# gal_pla_smd_ii.net
KiCad netlist of a schematic drawn in EAGLE
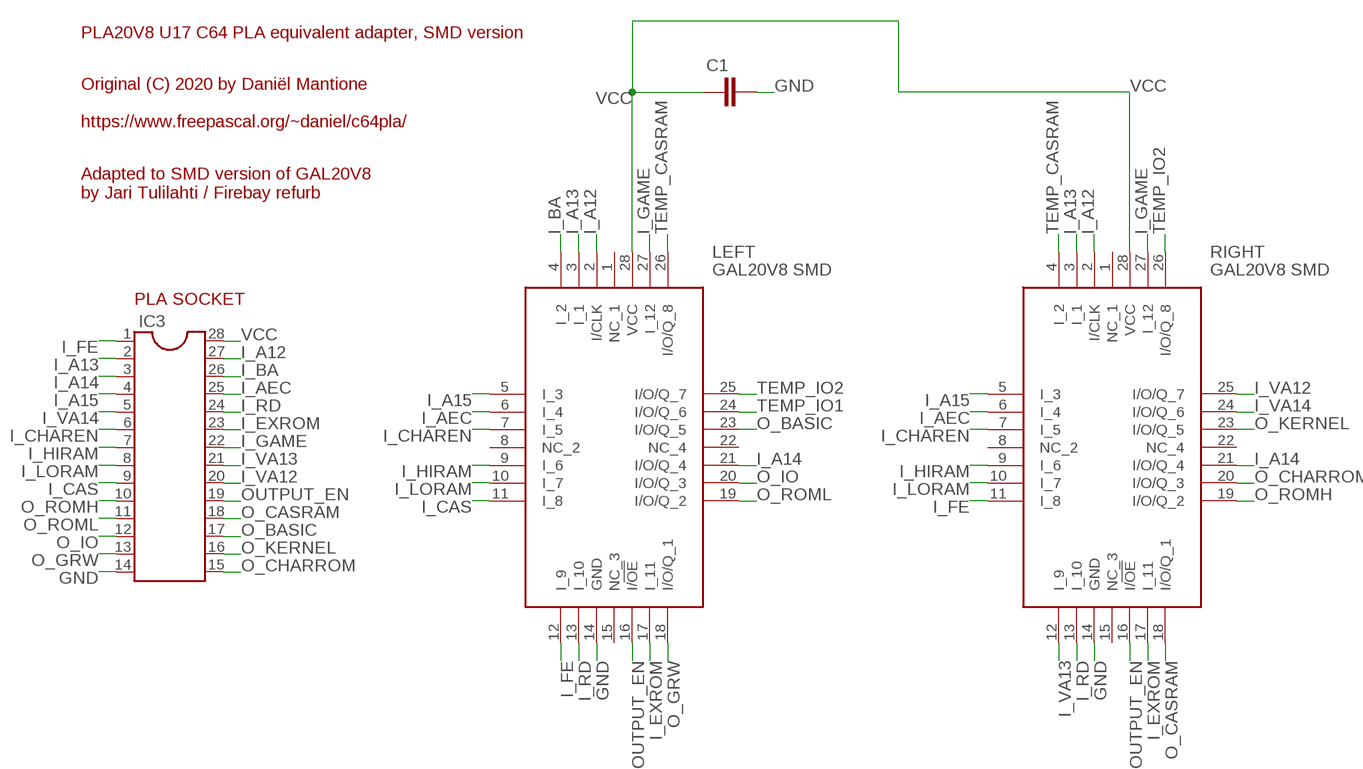
[diagram p0: schematic, sheet 1]

(export (version "E")
  (design (tool "Eeschema 10.0.6"))
  (components
    (comp (ref "C1")
      (value "CAP0603-CAP")
      (footprint "eagle-import:0603-CAP")
      (libsource (lib "eagle-import") (part "CAP0603-CAP"))
    )
    (comp (ref "IC3")
      (value "DIL28")
      (footprint "eagle-import:DIL28-6")
      (libsource (lib "eagle-import") (part "DIL28"))
    )
    (comp (ref "LEFT")
      (value "GAL20V8 SMD")
      (footprint "eagle-import:PLCC127P1245X1245X457-28N")
      (fields (field (name "MANUFACTURER_PART_NUMBER") "GAL20V8B-10LJI"))
      (libsource (lib "eagle-import") (part "GAL20V8B-10LJI"))
    )
    (comp (ref "RIGHT")
      (value "GAL20V8 SMD")
      (footprint "eagle-import:PLCC127P1245X1245X457-28N")
      (fields (field (name "MANUFACTURER_PART_NUMBER") "GAL20V8B-10LJI"))
      (libsource (lib "eagle-import") (part "GAL20V8B-10LJI"))
    )
  )
  (nets
    (net (code "1") (name "GND") (class "Default")
      (node (ref "C1") (pin "2") (pinfunction "2_2") (pintype "passive"))
      (node (ref "IC3") (pin "14") (pinfunction "14_14") (pintype "passive"))
      (node (ref "LEFT") (pin "14") (pinfunction "GND_14") (pintype "bidirectional"))
      (node (ref "RIGHT") (pin "14") (pinfunction "GND_14") (pintype "bidirectional"))
    )
    (net (code "2") (name "I_A12") (class "Default")
      (node (ref "IC3") (pin "27") (pinfunction "27_27") (pintype "passive"))
      (node (ref "LEFT") (pin "2") (pinfunction "I/CLK_2") (pintype "bidirectional"))
      (node (ref "RIGHT") (pin "2") (pinfunction "I/CLK_2") (pintype "bidirectional"))
    )
    (net (code "3") (name "I_A13") (class "Default")
      (node (ref "IC3") (pin "2") (pinfunction "2_2") (pintype "passive"))
      (node (ref "LEFT") (pin "3") (pinfunction "I_1_3") (pintype "bidirectional"))
      (node (ref "RIGHT") (pin "3") (pinfunction "I_1_3") (pintype "bidirectional"))
    )
    (net (code "4") (name "I_A14") (class "Default")
      (node (ref "IC3") (pin "3") (pinfunction "3_3") (pintype "passive"))
      (node (ref "LEFT") (pin "21") (pinfunction "I/O/Q_4_21") (pintype "bidirectional"))
      (node (ref "RIGHT") (pin "21") (pinfunction "I/O/Q_4_21") (pintype "bidirectional"))
    )
    (net (code "5") (name "I_A15") (class "Default")
      (node (ref "IC3") (pin "4") (pinfunction "4_4") (pintype "passive"))
      (node (ref "LEFT") (pin "5") (pinfunction "I_3_5") (pintype "bidirectional"))
      (node (ref "RIGHT") (pin "5") (pinfunction "I_3_5") (pintype "bidirectional"))
    )
    (net (code "6") (name "I_AEC") (class "Default")
      (node (ref "IC3") (pin "25") (pinfunction "25_25") (pintype "passive"))
      (node (ref "LEFT") (pin "6") (pinfunction "I_4_6") (pintype "bidirectional"))
      (node (ref "RIGHT") (pin "6") (pinfunction "I_4_6") (pintype "bidirectional"))
    )
    (net (code "7") (name "I_BA") (class "Default")
      (node (ref "IC3") (pin "26") (pinfunction "26_26") (pintype "passive"))
      (node (ref "LEFT") (pin "4") (pinfunction "I_2_4") (pintype "bidirectional"))
    )
    (net (code "8") (name "I_CAS") (class "Default")
      (node (ref "IC3") (pin "9") (pinfunction "9_9") (pintype "passive"))
      (node (ref "LEFT") (pin "11") (pinfunction "I_8_11") (pintype "bidirectional"))
    )
    (net (code "9") (name "I_CHAREN") (class "Default")
      (node (ref "IC3") (pin "6") (pinfunction "6_6") (pintype "passive"))
      (node (ref "LEFT") (pin "7") (pinfunction "I_5_7") (pintype "bidirectional"))
      (node (ref "RIGHT") (pin "7") (pinfunction "I_5_7") (pintype "bidirectional"))
    )
    (net (code "10") (name "I_EXROM") (class "Default")
      (node (ref "IC3") (pin "23") (pinfunction "23_23") (pintype "passive"))
      (node (ref "LEFT") (pin "17") (pinfunction "I_11_17") (pintype "bidirectional"))
      (node (ref "RIGHT") (pin "17") (pinfunction "I_11_17") (pintype "bidirectional"))
    )
    (net (code "11") (name "I_FE") (class "Default")
      (node (ref "IC3") (pin "1") (pinfunction "1_1") (pintype "passive"))
      (node (ref "LEFT") (pin "12") (pinfunction "I_9_12") (pintype "bidirectional"))
      (node (ref "RIGHT") (pin "11") (pinfunction "I_8_11") (pintype "bidirectional"))
    )
    (net (code "12") (name "I_GAME") (class "Default")
      (node (ref "IC3") (pin "22") (pinfunction "22_22") (pintype "passive"))
      (node (ref "LEFT") (pin "27") (pinfunction "I_12_27") (pintype "bidirectional"))
      (node (ref "RIGHT") (pin "27") (pinfunction "I_12_27") (pintype "bidirectional"))
    )
    (net (code "13") (name "I_HIRAM") (class "Default")
      (node (ref "IC3") (pin "7") (pinfunction "7_7") (pintype "passive"))
      (node (ref "LEFT") (pin "9") (pinfunction "I_6_9") (pintype "bidirectional"))
      (node (ref "RIGHT") (pin "9") (pinfunction "I_6_9") (pintype "bidirectional"))
    )
    (net (code "14") (name "I_LORAM") (class "Default")
      (node (ref "IC3") (pin "8") (pinfunction "8_8") (pintype "passive"))
      (node (ref "LEFT") (pin "10") (pinfunction "I_7_10") (pintype "bidirectional"))
      (node (ref "RIGHT") (pin "10") (pinfunction "I_7_10") (pintype "bidirectional"))
    )
    (net (code "15") (name "I_RD") (class "Default")
      (node (ref "IC3") (pin "24") (pinfunction "24_24") (pintype "passive"))
      (node (ref "LEFT") (pin "13") (pinfunction "I_10_13") (pintype "bidirectional"))
      (node (ref "RIGHT") (pin "13") (pinfunction "I_10_13") (pintype "bidirectional"))
    )
    (net (code "16") (name "I_VA12") (class "Default")
      (node (ref "IC3") (pin "20") (pinfunction "20_20") (pintype "passive"))
      (node (ref "RIGHT") (pin "25") (pinfunction "I/O/Q_7_25") (pintype "bidirectional"))
    )
    (net (code "17") (name "I_VA13") (class "Default")
      (node (ref "IC3") (pin "21") (pinfunction "21_21") (pintype "passive"))
      (node (ref "RIGHT") (pin "12") (pinfunction "I_9_12") (pintype "bidirectional"))
    )
    (net (code "18") (name "I_VA14") (class "Default")
      (node (ref "IC3") (pin "5") (pinfunction "5_5") (pintype "passive"))
      (node (ref "RIGHT") (pin "24") (pinfunction "I/O/Q_6_24") (pintype "bidirectional"))
    )
    (net (code "19") (name "OUTPUT_EN") (class "Default")
      (node (ref "IC3") (pin "19") (pinfunction "19_19") (pintype "passive"))
      (node (ref "LEFT") (pin "16") (pinfunction "I/~{OE}_16") (pintype "bidirectional"))
      (node (ref "RIGHT") (pin "16") (pinfunction "I/~{OE}_16") (pintype "bidirectional"))
    )
    (net (code "20") (name "O_BASIC") (class "Default")
      (node (ref "IC3") (pin "17") (pinfunction "17_17") (pintype "passive"))
      (node (ref "LEFT") (pin "23") (pinfunction "I/O/Q_5_23") (pintype "bidirectional"))
    )
    (net (code "21") (name "O_CASRAM") (class "Default")
      (node (ref "IC3") (pin "18") (pinfunction "18_18") (pintype "passive"))
      (node (ref "RIGHT") (pin "18") (pinfunction "I/O/Q_1_18") (pintype "bidirectional"))
    )
    (net (code "22") (name "O_CHARROM") (class "Default")
      (node (ref "IC3") (pin "15") (pinfunction "15_15") (pintype "passive"))
      (node (ref "RIGHT") (pin "20") (pinfunction "I/O/Q_3_20") (pintype "bidirectional"))
    )
    (net (code "23") (name "O_GRW") (class "Default")
      (node (ref "IC3") (pin "13") (pinfunction "13_13") (pintype "passive"))
      (node (ref "LEFT") (pin "18") (pinfunction "I/O/Q_1_18") (pintype "bidirectional"))
    )
    (net (code "24") (name "O_IO") (class "Default")
      (node (ref "IC3") (pin "12") (pinfunction "12_12") (pintype "passive"))
      (node (ref "LEFT") (pin "20") (pinfunction "I/O/Q_3_20") (pintype "bidirectional"))
    )
    (net (code "25") (name "O_KERNEL") (class "Default")
      (node (ref "IC3") (pin "16") (pinfunction "16_16") (pintype "passive"))
      (node (ref "RIGHT") (pin "23") (pinfunction "I/O/Q_5_23") (pintype "bidirectional"))
    )
    (net (code "26") (name "O_ROMH") (class "Default")
      (node (ref "IC3") (pin "10") (pinfunction "10_10") (pintype "passive"))
      (node (ref "RIGHT") (pin "19") (pinfunction "I/O/Q_2_19") (pintype "bidirectional"))
    )
    (net (code "27") (name "O_ROML") (class "Default")
      (node (ref "IC3") (pin "11") (pinfunction "11_11") (pintype "passive"))
      (node (ref "LEFT") (pin "19") (pinfunction "I/O/Q_2_19") (pintype "bidirectional"))
    )
    (net (code "28") (name "TEMP_CASRAM") (class "Default")
      (node (ref "LEFT") (pin "26") (pinfunction "I/O/Q_8_26") (pintype "bidirectional"))
      (node (ref "RIGHT") (pin "4") (pinfunction "I_2_4") (pintype "bidirectional"))
    )
    (net (code "29") (name "TEMP_IO1") (class "Default")
      (node (ref "LEFT") (pin "24") (pinfunction "I/O/Q_6_24") (pintype "bidirectional"))
    )
    (net (code "30") (name "TEMP_IO2") (class "Default")
      (node (ref "LEFT") (pin "25") (pinfunction "I/O/Q_7_25") (pintype "bidirectional"))
      (node (ref "RIGHT") (pin "26") (pinfunction "I/O/Q_8_26") (pintype "bidirectional"))
    )
    (net (code "31") (name "VCC") (class "Default")
      (node (ref "C1") (pin "1") (pinfunction "1_1") (pintype "passive"))
      (node (ref "IC3") (pin "28") (pinfunction "28_28") (pintype "passive"))
      (node (ref "LEFT") (pin "28") (pinfunction "VCC_28") (pintype "bidirectional"))
      (node (ref "RIGHT") (pin "28") (pinfunction "VCC_28") (pintype "bidirectional"))
    )
    (net (code "32") (name "unconnected-(LEFT-NC_1-Pad1)") (class "Default")
      (node (ref "LEFT") (pin "1") (pinfunction "NC_1_1") (pintype "bidirectional"))
    )
    (net (code "33") (name "unconnected-(LEFT-NC_2-Pad8)") (class "Default")
      (node (ref "LEFT") (pin "8") (pinfunction "NC_2_8") (pintype "bidirectional"))
    )
    (net (code "34") (name "unconnected-(LEFT-NC_3-Pad15)") (class "Default")
      (node (ref "LEFT") (pin "15") (pinfunction "NC_3_15") (pintype "bidirectional"))
    )
    (net (code "35") (name "unconnected-(LEFT-NC_4-Pad22)") (class "Default")
      (node (ref "LEFT") (pin "22") (pinfunction "NC_4_22") (pintype "bidirectional"))
    )
    (net (code "36") (name "unconnected-(RIGHT-NC_1-Pad1)") (class "Default")
      (node (ref "RIGHT") (pin "1") (pinfunction "NC_1_1") (pintype "bidirectional"))
    )
    (net (code "37") (name "unconnected-(RIGHT-NC_2-Pad8)") (class "Default")
      (node (ref "RIGHT") (pin "8") (pinfunction "NC_2_8") (pintype "bidirectional"))
    )
    (net (code "38") (name "unconnected-(RIGHT-NC_3-Pad15)") (class "Default")
      (node (ref "RIGHT") (pin "15") (pinfunction "NC_3_15") (pintype "bidirectional"))
    )
    (net (code "39") (name "unconnected-(RIGHT-NC_4-Pad22)") (class "Default")
      (node (ref "RIGHT") (pin "22") (pinfunction "NC_4_22") (pintype "bidirectional"))
    )
  )
)
